# ads1292_Dorokhov.net
KiCad netlist of a schematic drawn in EAGLE
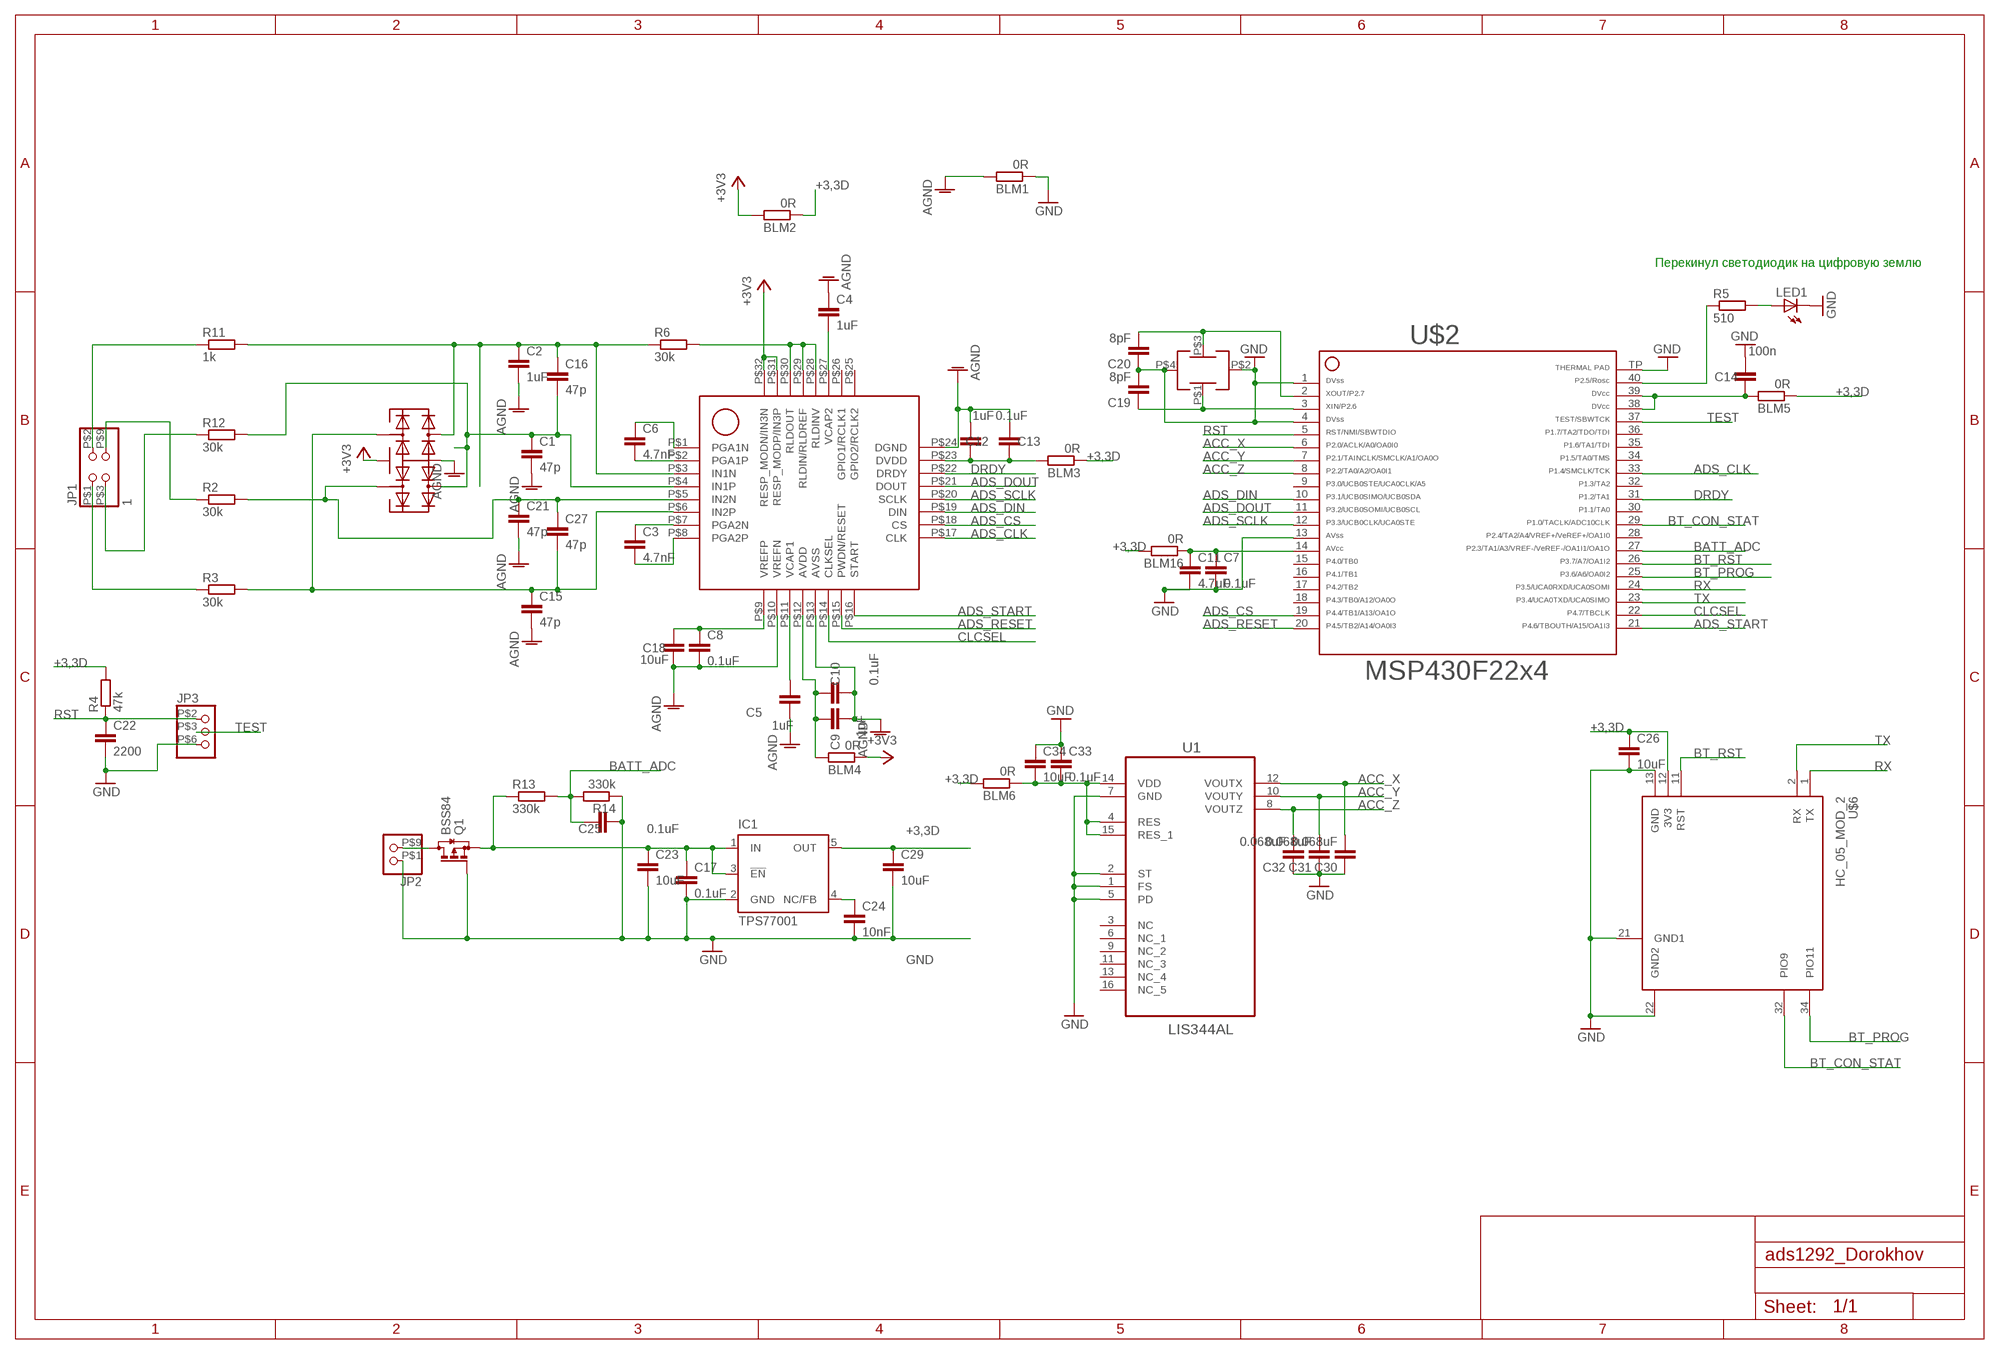
[diagram p0: schematic, sheet 1]

(export (version "E")
  (design (tool "Eeschema 10.0.6"))
  (components
    (comp (ref "BLM1")
      (value "0R")
      (footprint "eagle-import:SMD_0402")
      (libsource (lib "eagle-import") (part "RES0402"))
    )
    (comp (ref "BLM2")
      (value "0R")
      (footprint "eagle-import:SMD_0402")
      (libsource (lib "eagle-import") (part "RES0402"))
    )
    (comp (ref "BLM3")
      (value "0R")
      (footprint "eagle-import:SMD_0402")
      (libsource (lib "eagle-import") (part "RES0402"))
    )
    (comp (ref "BLM4")
      (value "0R")
      (footprint "eagle-import:SMD_0402")
      (libsource (lib "eagle-import") (part "RES0402"))
    )
    (comp (ref "BLM5")
      (value "0R")
      (footprint "eagle-import:SMD_0402")
      (libsource (lib "eagle-import") (part "RES0402"))
    )
    (comp (ref "BLM6")
      (value "0R")
      (footprint "eagle-import:SMD_0402")
      (libsource (lib "eagle-import") (part "RES0402"))
    )
    (comp (ref "BLM16")
      (value "0R")
      (footprint "eagle-import:SMD_0402")
      (libsource (lib "eagle-import") (part "RES0402"))
    )
    (comp (ref "C1")
      (value "47p")
      (footprint "eagle-import:SMD_0402")
      (libsource (lib "eagle-import") (part "CAP0402"))
    )
    (comp (ref "C2")
      (value "1uF")
      (footprint "eagle-import:SMD_0603")
      (libsource (lib "eagle-import") (part "CAP0603"))
    )
    (comp (ref "C3")
      (value "4.7nF")
      (footprint "eagle-import:SMD_0402")
      (libsource (lib "eagle-import") (part "CAP0402"))
    )
    (comp (ref "C4")
      (value "1uF")
      (footprint "eagle-import:SMD_0402")
      (libsource (lib "eagle-import") (part "CAP0402"))
    )
    (comp (ref "C5")
      (value "1uF")
      (footprint "eagle-import:SMD_0402")
      (libsource (lib "eagle-import") (part "CAP0402"))
    )
    (comp (ref "C6")
      (value "4.7nF")
      (footprint "eagle-import:SMD_0402")
      (libsource (lib "eagle-import") (part "CAP0402"))
    )
    (comp (ref "C7")
      (value "0.1uF")
      (footprint "eagle-import:SMD_0402")
      (libsource (lib "eagle-import") (part "CAP0402"))
    )
    (comp (ref "C8")
      (value "0.1uF")
      (footprint "eagle-import:SMD_0402")
      (libsource (lib "eagle-import") (part "CAP0402"))
    )
    (comp (ref "C9")
      (value "1uF")
      (footprint "eagle-import:SMD_0402")
      (libsource (lib "eagle-import") (part "CAP0402"))
    )
    (comp (ref "C10")
      (value "0.1uF")
      (footprint "eagle-import:SMD_0402")
      (libsource (lib "eagle-import") (part "CAP0402"))
    )
    (comp (ref "C11")
      (value "4.7uF")
      (footprint "eagle-import:SMD_0603")
      (libsource (lib "eagle-import") (part "CAP0603"))
    )
    (comp (ref "C12")
      (value "1uF")
      (footprint "eagle-import:SMD_0402")
      (libsource (lib "eagle-import") (part "CAP0402"))
    )
    (comp (ref "C13")
      (value "0.1uF")
      (footprint "eagle-import:SMD_0402")
      (libsource (lib "eagle-import") (part "CAP0402"))
    )
    (comp (ref "C14")
      (value "100n")
      (footprint "eagle-import:SMD_0402")
      (libsource (lib "eagle-import") (part "CAP0402"))
    )
    (comp (ref "C15")
      (value "47p")
      (footprint "eagle-import:SMD_0402")
      (libsource (lib "eagle-import") (part "CAP0402"))
    )
    (comp (ref "C16")
      (value "47p")
      (footprint "eagle-import:SMD_0402")
      (libsource (lib "eagle-import") (part "CAP0402"))
    )
    (comp (ref "C17")
      (value "0.1uF")
      (footprint "eagle-import:SMD_0402")
      (libsource (lib "eagle-import") (part "CAP0402"))
    )
    (comp (ref "C18")
      (value "10uF")
      (footprint "eagle-import:SMD_0603")
      (libsource (lib "eagle-import") (part "CAP0603"))
    )
    (comp (ref "C19")
      (value "8pF")
      (footprint "eagle-import:SMD_0402")
      (libsource (lib "eagle-import") (part "CAP0402"))
    )
    (comp (ref "C20")
      (value "8pF")
      (footprint "eagle-import:SMD_0402")
      (libsource (lib "eagle-import") (part "CAP0402"))
    )
    (comp (ref "C21")
      (value "47p")
      (footprint "eagle-import:SMD_0402")
      (libsource (lib "eagle-import") (part "CAP0402"))
    )
    (comp (ref "C22")
      (value "2200")
      (footprint "eagle-import:SMD_0402")
      (libsource (lib "eagle-import") (part "CAP0402"))
    )
    (comp (ref "C23")
      (value "10uF")
      (footprint "eagle-import:SMD_0603")
      (libsource (lib "eagle-import") (part "CAP0603"))
    )
    (comp (ref "C24")
      (value "10nF")
      (footprint "eagle-import:SMD_0402")
      (libsource (lib "eagle-import") (part "CAP0402"))
    )
    (comp (ref "C25")
      (value "0.1uF")
      (footprint "eagle-import:SMD_0402")
      (libsource (lib "eagle-import") (part "CAP0402"))
    )
    (comp (ref "C26")
      (value "10uF")
      (footprint "eagle-import:SMD_0603")
      (libsource (lib "eagle-import") (part "CAP0603"))
    )
    (comp (ref "C27")
      (value "47p")
      (footprint "eagle-import:SMD_0402")
      (libsource (lib "eagle-import") (part "CAP0402"))
    )
    (comp (ref "C29")
      (value "10uF")
      (footprint "eagle-import:SMD_0603")
      (libsource (lib "eagle-import") (part "CAP0603"))
    )
    (comp (ref "C30")
      (value "0.068uF")
      (footprint "eagle-import:SMD_0402")
      (libsource (lib "eagle-import") (part "CAP0402"))
    )
    (comp (ref "C31")
      (value "0.068uF")
      (footprint "eagle-import:SMD_0402")
      (libsource (lib "eagle-import") (part "CAP0402"))
    )
    (comp (ref "C32")
      (value "0.068uF")
      (footprint "eagle-import:SMD_0402")
      (libsource (lib "eagle-import") (part "CAP0402"))
    )
    (comp (ref "C33")
      (value "0.1uF")
      (footprint "eagle-import:SMD_0402")
      (libsource (lib "eagle-import") (part "CAP0402"))
    )
    (comp (ref "C34")
      (value "10uF")
      (footprint "eagle-import:SMD_0603")
      (libsource (lib "eagle-import") (part "CAP0603"))
    )
    (comp (ref "IC1")
      (value "TPS77001")
      (footprint "eagle-import:SOT23-DBV")
      (fields (field (name "MF") "TEXAS INSTRUMENTS") (field (name "MPN") "TPS77001DBVT"))
      (libsource (lib "eagle-import") (part "TPS77001"))
    )
    (comp (ref "JP1")
      (value "1")
      (footprint "eagle-import:PINHEAD_SMD_2X2_2,5")
      (libsource (lib "eagle-import") (part "PINHD-2X2SMD_2,5"))
    )
    (comp (ref "JP2")
      (value "PINHD-1X2SMD_2,5")
      (footprint "eagle-import:PINHEAD_SMD_2X1_2,5")
      (libsource (lib "eagle-import") (part "PINHD-1X2SMD_2,5"))
    )
    (comp (ref "JP3")
      (value "PINHD-1X3PROG_SMD")
      (footprint "eagle-import:PROG_CONNECTOR_3PIN")
      (libsource (lib "eagle-import") (part "PINHD-1X3PROG_SMD"))
    )
    (comp (ref "LED1")
      (value "LEDSML0603")
      (footprint "eagle-import:SML0603")
      (libsource (lib "eagle-import") (part "LEDSML0603"))
    )
    (comp (ref "Q1")
      (value "BSS84")
      (footprint "eagle-import:SOT23")
      (libsource (lib "eagle-import") (part "BSS84"))
    )
    (comp (ref "R2")
      (value "30k")
      (footprint "eagle-import:R0603")
      (libsource (lib "eagle-import") (part "RESR0603_WIDE"))
    )
    (comp (ref "R3")
      (value "30k")
      (footprint "eagle-import:R0603")
      (libsource (lib "eagle-import") (part "RESR0603_WIDE"))
    )
    (comp (ref "R4")
      (value "47k")
      (footprint "eagle-import:SMD_0402")
      (libsource (lib "eagle-import") (part "RES0402"))
    )
    (comp (ref "R5")
      (value "510")
      (footprint "eagle-import:SMD_0402")
      (libsource (lib "eagle-import") (part "RES0402"))
    )
    (comp (ref "R6")
      (value "30k")
      (footprint "eagle-import:SMD_0402")
      (libsource (lib "eagle-import") (part "RES0402"))
    )
    (comp (ref "R11")
      (value "1k")
      (footprint "eagle-import:R0603")
      (libsource (lib "eagle-import") (part "RESR0603_WIDE"))
    )
    (comp (ref "R12")
      (value "30k")
      (footprint "eagle-import:R0603")
      (libsource (lib "eagle-import") (part "RESR0603_WIDE"))
    )
    (comp (ref "R13")
      (value "330k")
      (footprint "eagle-import:SMD_0402")
      (libsource (lib "eagle-import") (part "RES0402"))
    )
    (comp (ref "R14")
      (value "330k")
      (footprint "eagle-import:SMD_0402")
      (libsource (lib "eagle-import") (part "RES0402"))
    )
    (comp (ref "U$1")
      (value "ADS1292TQFP-32")
      (footprint "eagle-import:TQFP-32")
      (libsource (lib "eagle-import") (part "ADS1292TQFP-32"))
    )
    (comp (ref "U$2")
      (value "F22X4---RHA40")
      (footprint "eagle-import:RHA40")
      (libsource (lib "eagle-import") (part "F22X4---RHA40"))
    )
    (comp (ref "U$3")
      (value "ECS_16_CRYSTAL")
      (footprint "eagle-import:ECS_16_CRYSTAL")
      (libsource (lib "eagle-import") (part "ECS_16_CRYSTAL"))
    )
    (comp (ref "U$4")
      (value "DALC208")
      (footprint "eagle-import:SOT23-6")
      (libsource (lib "eagle-import") (part "DALC208"))
    )
    (comp (ref "U$6")
      (value "HC_05_MOD_2")
      (footprint "eagle-import:BLUETOOTH_SMD_MOD2")
      (libsource (lib "eagle-import") (part "HC_05_MOD_2"))
    )
    (comp (ref "U1")
      (value "LIS344AL")
      (footprint "eagle-import:LGA16R65P4X4_400X400X160")
      (libsource (lib "eagle-import") (part "LIS344AL"))
    )
  )
  (nets
    (net (code "1") (name "+3V3") (class "Default")
      (node (ref "BLM2") (pin "P$4") (pinfunction "2_P$4") (pintype "passive"))
      (node (ref "BLM4") (pin "P$3") (pinfunction "1_P$3") (pintype "passive"))
      (node (ref "U$1") (pin "P$31") (pinfunction "RESP_MODP/IN3P_P$31") (pintype "bidirectional"))
      (node (ref "U$1") (pin "P$32") (pinfunction "RESP_MODN/IN3N_P$32") (pintype "bidirectional"))
      (node (ref "U$4") (pin "2") (pinfunction "2_2") (pintype "passive"))
    )
    (net (code "2") (name "/+3,3D") (class "Default")
      (node (ref "BLM16") (pin "P$4") (pinfunction "2_P$4") (pintype "passive"))
      (node (ref "BLM2") (pin "P$3") (pinfunction "1_P$3") (pintype "passive"))
      (node (ref "BLM3") (pin "P$3") (pinfunction "1_P$3") (pintype "passive"))
      (node (ref "BLM5") (pin "P$3") (pinfunction "1_P$3") (pintype "passive"))
      (node (ref "BLM6") (pin "P$4") (pinfunction "2_P$4") (pintype "passive"))
      (node (ref "C26") (pin "P$1") (pinfunction "1_P$1") (pintype "passive"))
      (node (ref "C29") (pin "P$1") (pinfunction "1_P$1") (pintype "passive"))
      (node (ref "IC1") (pin "5") (pinfunction "OUT_5") (pintype "passive"))
      (node (ref "R4") (pin "P$4") (pinfunction "2_P$4") (pintype "passive"))
      (node (ref "U$6") (pin "12") (pinfunction "3V3_12") (pintype "bidirectional"))
    )
    (net (code "3") (name "/ACC_X") (class "Default")
      (node (ref "C30") (pin "P$4") (pinfunction "2_P$4") (pintype "passive"))
      (node (ref "U$2") (pin "6") (pinfunction "6_6") (pintype "bidirectional"))
      (node (ref "U1") (pin "12") (pinfunction "VOUTX_12") (pintype "output"))
    )
    (net (code "4") (name "/ACC_Y") (class "Default")
      (node (ref "C31") (pin "P$4") (pinfunction "2_P$4") (pintype "passive"))
      (node (ref "U$2") (pin "7") (pinfunction "7_7") (pintype "bidirectional"))
      (node (ref "U1") (pin "10") (pinfunction "VOUTY_10") (pintype "output"))
    )
    (net (code "5") (name "/ACC_Z") (class "Default")
      (node (ref "C32") (pin "P$4") (pinfunction "2_P$4") (pintype "passive"))
      (node (ref "U$2") (pin "8") (pinfunction "8_8") (pintype "bidirectional"))
      (node (ref "U1") (pin "8") (pinfunction "VOUTZ_8") (pintype "output"))
    )
    (net (code "6") (name "/ADS_CLK") (class "Default")
      (node (ref "U$1") (pin "P$17") (pinfunction "CLK_P$17") (pintype "bidirectional"))
      (node (ref "U$2") (pin "33") (pinfunction "33_33") (pintype "bidirectional"))
    )
    (net (code "7") (name "/ADS_CS") (class "Default")
      (node (ref "U$1") (pin "P$18") (pinfunction "CS_P$18") (pintype "bidirectional"))
      (node (ref "U$2") (pin "19") (pinfunction "19_19") (pintype "bidirectional"))
    )
    (net (code "8") (name "/ADS_DIN") (class "Default")
      (node (ref "U$1") (pin "P$19") (pinfunction "DIN_P$19") (pintype "bidirectional"))
      (node (ref "U$2") (pin "10") (pinfunction "10_10") (pintype "bidirectional"))
    )
    (net (code "9") (name "/ADS_DOUT") (class "Default")
      (node (ref "U$1") (pin "P$21") (pinfunction "DOUT_P$21") (pintype "bidirectional"))
      (node (ref "U$2") (pin "11") (pinfunction "11_11") (pintype "bidirectional"))
    )
    (net (code "10") (name "/ADS_RESET") (class "Default")
      (node (ref "U$1") (pin "P$15") (pinfunction "PWDN/RESET_P$15") (pintype "bidirectional"))
      (node (ref "U$2") (pin "20") (pinfunction "20_20") (pintype "bidirectional"))
    )
    (net (code "11") (name "/ADS_SCLK") (class "Default")
      (node (ref "U$1") (pin "P$20") (pinfunction "SCLK_P$20") (pintype "bidirectional"))
      (node (ref "U$2") (pin "12") (pinfunction "12_12") (pintype "bidirectional"))
    )
    (net (code "12") (name "/ADS_START") (class "Default")
      (node (ref "U$1") (pin "P$16") (pinfunction "START_P$16") (pintype "bidirectional"))
      (node (ref "U$2") (pin "21") (pinfunction "21_21") (pintype "bidirectional"))
    )
    (net (code "13") (name "/BATT_ADC") (class "Default")
      (node (ref "C25") (pin "P$3") (pinfunction "1_P$3") (pintype "passive"))
      (node (ref "R13") (pin "P$4") (pinfunction "2_P$4") (pintype "passive"))
      (node (ref "R14") (pin "P$4") (pinfunction "2_P$4") (pintype "passive"))
      (node (ref "U$2") (pin "27") (pinfunction "27_27") (pintype "bidirectional"))
    )
    (net (code "14") (name "/BT_CON_STAT") (class "Default")
      (node (ref "U$2") (pin "29") (pinfunction "29_29") (pintype "bidirectional"))
      (node (ref "U$6") (pin "32") (pinfunction "PIO9_32") (pintype "bidirectional"))
    )
    (net (code "15") (name "/BT_PROG") (class "Default")
      (node (ref "U$2") (pin "25") (pinfunction "25_25") (pintype "bidirectional"))
      (node (ref "U$6") (pin "34") (pinfunction "PIO11_34") (pintype "bidirectional"))
    )
    (net (code "16") (name "/BT_RST") (class "Default")
      (node (ref "U$2") (pin "26") (pinfunction "26_26") (pintype "bidirectional"))
      (node (ref "U$6") (pin "11") (pinfunction "RST_11") (pintype "bidirectional"))
    )
    (net (code "17") (name "/CLCSEL") (class "Default")
      (node (ref "U$1") (pin "P$14") (pinfunction "CLKSEL_P$14") (pintype "bidirectional"))
      (node (ref "U$2") (pin "22") (pinfunction "22_22") (pintype "bidirectional"))
    )
    (net (code "18") (name "/DRDY") (class "Default")
      (node (ref "U$1") (pin "P$22") (pinfunction "DRDY_P$22") (pintype "bidirectional"))
      (node (ref "U$2") (pin "31") (pinfunction "31_31") (pintype "bidirectional"))
    )
    (net (code "19") (name "/RST") (class "Default")
      (node (ref "C22") (pin "P$3") (pinfunction "1_P$3") (pintype "passive"))
      (node (ref "JP3") (pin "P$2") (pinfunction "1_P$2") (pintype "passive"))
      (node (ref "R4") (pin "P$3") (pinfunction "1_P$3") (pintype "passive"))
      (node (ref "U$2") (pin "5") (pinfunction "5_5") (pintype "bidirectional"))
    )
    (net (code "20") (name "/RX") (class "Default")
      (node (ref "U$2") (pin "24") (pinfunction "24_24") (pintype "bidirectional"))
      (node (ref "U$6") (pin "1") (pinfunction "TX_1") (pintype "bidirectional"))
    )
    (net (code "21") (name "/TEST") (class "Default")
      (node (ref "JP3") (pin "P$3") (pinfunction "2_P$3") (pintype "passive"))
      (node (ref "U$2") (pin "37") (pinfunction "37_37") (pintype "input"))
    )
    (net (code "22") (name "/TX") (class "Default")
      (node (ref "U$2") (pin "23") (pinfunction "23_23") (pintype "bidirectional"))
      (node (ref "U$6") (pin "2") (pinfunction "RX_2") (pintype "bidirectional"))
    )
    (net (code "23") (name "AGND") (class "Default")
      (node (ref "BLM1") (pin "P$4") (pinfunction "2_P$4") (pintype "passive"))
      (node (ref "C1") (pin "P$4") (pinfunction "2_P$4") (pintype "passive"))
      (node (ref "C10") (pin "P$4") (pinfunction "2_P$4") (pintype "passive"))
      (node (ref "C12") (pin "P$4") (pinfunction "2_P$4") (pintype "passive"))
      (node (ref "C13") (pin "P$4") (pinfunction "2_P$4") (pintype "passive"))
      (node (ref "C15") (pin "P$4") (pinfunction "2_P$4") (pintype "passive"))
      (node (ref "C18") (pin "P$2") (pinfunction "2_P$2") (pintype "passive"))
      (node (ref "C2") (pin "P$2") (pinfunction "2_P$2") (pintype "passive"))
      (node (ref "C21") (pin "P$4") (pinfunction "2_P$4") (pintype "passive"))
      (node (ref "C4") (pin "P$3") (pinfunction "1_P$3") (pintype "passive"))
      (node (ref "C5") (pin "P$4") (pinfunction "2_P$4") (pintype "passive"))
      (node (ref "C8") (pin "P$4") (pinfunction "2_P$4") (pintype "passive"))
      (node (ref "C9") (pin "P$4") (pinfunction "2_P$4") (pintype "passive"))
      (node (ref "U$1") (pin "P$10") (pinfunction "VREFN_P$10") (pintype "bidirectional"))
      (node (ref "U$1") (pin "P$13") (pinfunction "AVSS_P$13") (pintype "bidirectional"))
      (node (ref "U$1") (pin "P$24") (pinfunction "DGND_P$24") (pintype "bidirectional"))
      (node (ref "U$4") (pin "5") (pinfunction "5_5") (pintype "passive"))
    )
    (net (code "24") (name "GND") (class "Default")
      (node (ref "BLM1") (pin "P$3") (pinfunction "1_P$3") (pintype "passive"))
      (node (ref "C11") (pin "P$2") (pinfunction "2_P$2") (pintype "passive"))
      (node (ref "C14") (pin "P$4") (pinfunction "2_P$4") (pintype "passive"))
      (node (ref "C17") (pin "P$4") (pinfunction "2_P$4") (pintype "passive"))
      (node (ref "C19") (pin "P$4") (pinfunction "2_P$4") (pintype "passive"))
      (node (ref "C20") (pin "P$3") (pinfunction "1_P$3") (pintype "passive"))
      (node (ref "C22") (pin "P$4") (pinfunction "2_P$4") (pintype "passive"))
      (node (ref "C23") (pin "P$2") (pinfunction "2_P$2") (pintype "passive"))
      (node (ref "C24") (pin "P$4") (pinfunction "2_P$4") (pintype "passive"))
      (node (ref "C25") (pin "P$4") (pinfunction "2_P$4") (pintype "passive"))
      (node (ref "C26") (pin "P$2") (pinfunction "2_P$2") (pintype "passive"))
      (node (ref "C29") (pin "P$2") (pinfunction "2_P$2") (pintype "passive"))
      (node (ref "C30") (pin "P$3") (pinfunction "1_P$3") (pintype "passive"))
      (node (ref "C31") (pin "P$3") (pinfunction "1_P$3") (pintype "passive"))
      (node (ref "C32") (pin "P$3") (pinfunction "1_P$3") (pintype "passive"))
      (node (ref "C33") (pin "P$3") (pinfunction "1_P$3") (pintype "passive"))
      (node (ref "C34") (pin "P$1") (pinfunction "1_P$1") (pintype "passive"))
      (node (ref "C7") (pin "P$4") (pinfunction "2_P$4") (pintype "passive"))
      (node (ref "IC1") (pin "2") (pinfunction "GND_2") (pintype "power_in"))
      (node (ref "JP2") (pin "P$1") (pinfunction "1_P$1") (pintype "passive"))
      (node (ref "JP3") (pin "P$6") (pinfunction "3_P$6") (pintype "passive"))
      (node (ref "LED1") (pin "C") (pinfunction "C_C") (pintype "passive"))
      (node (ref "Q1") (pin "1") (pinfunction "G_1") (pintype "passive"))
      (node (ref "R14") (pin "P$3") (pinfunction "1_P$3") (pintype "passive"))
      (node (ref "U$2") (pin "1") (pinfunction "1_1") (pintype "power_in"))
      (node (ref "U$2") (pin "13") (pinfunction "13_13") (pintype "power_in"))
      (node (ref "U$2") (pin "4") (pinfunction "4_4") (pintype "power_in"))
      (node (ref "U$2") (pin "TP") (pinfunction "TP_TP") (pintype "power_in"))
      (node (ref "U$3") (pin "P$2") (pinfunction "P$2_P$2") (pintype "bidirectional"))
      (node (ref "U$3") (pin "P$4") (pinfunction "P$3_P$4") (pintype "bidirectional"))
      (node (ref "U$6") (pin "13") (pinfunction "GND_13") (pintype "bidirectional"))
      (node (ref "U$6") (pin "21") (pinfunction "GND1_21") (pintype "bidirectional"))
      (node (ref "U$6") (pin "22") (pinfunction "GND2_22") (pintype "bidirectional"))
      (node (ref "U1") (pin "1") (pinfunction "FS_1") (pintype "passive"))
      (node (ref "U1") (pin "2") (pinfunction "ST_2") (pintype "passive"))
      (node (ref "U1") (pin "5") (pinfunction "PD_5") (pintype "passive"))
      (node (ref "U1") (pin "7") (pinfunction "GND_7") (pintype "passive"))
    )
    (net (code "25") (name "Net-(BLM3-2)") (class "Default")
      (node (ref "BLM3") (pin "P$4") (pinfunction "2_P$4") (pintype "passive"))
      (node (ref "C12") (pin "P$3") (pinfunction "1_P$3") (pintype "passive"))
      (node (ref "C13") (pin "P$3") (pinfunction "1_P$3") (pintype "passive"))
      (node (ref "U$1") (pin "P$23") (pinfunction "DVDD_P$23") (pintype "bidirectional"))
    )
    (net (code "26") (name "Net-(BLM4-2)") (class "Default")
      (node (ref "BLM4") (pin "P$4") (pinfunction "2_P$4") (pintype "passive"))
      (node (ref "C10") (pin "P$3") (pinfunction "1_P$3") (pintype "passive"))
      (node (ref "C9") (pin "P$3") (pinfunction "1_P$3") (pintype "passive"))
      (node (ref "U$1") (pin "P$12") (pinfunction "AVDD_P$12") (pintype "bidirectional"))
    )
    (net (code "27") (name "Net-(BLM5-2)") (class "Default")
      (node (ref "BLM5") (pin "P$4") (pinfunction "2_P$4") (pintype "passive"))
      (node (ref "C14") (pin "P$3") (pinfunction "1_P$3") (pintype "passive"))
      (node (ref "U$2") (pin "38") (pinfunction "38_38") (pintype "power_in"))
      (node (ref "U$2") (pin "39") (pinfunction "39_39") (pintype "power_in"))
    )
    (net (code "28") (name "Net-(BLM6-1)") (class "Default")
      (node (ref "BLM6") (pin "P$3") (pinfunction "1_P$3") (pintype "passive"))
      (node (ref "C33") (pin "P$4") (pinfunction "2_P$4") (pintype "passive"))
      (node (ref "C34") (pin "P$2") (pinfunction "2_P$2") (pintype "passive"))
      (node (ref "U1") (pin "14") (pinfunction "VDD_14") (pintype "power_in"))
      (node (ref "U1") (pin "15") (pinfunction "RES_1_15") (pintype "passive"))
      (node (ref "U1") (pin "4") (pinfunction "RES_4") (pintype "passive"))
    )
    (net (code "29") (name "Net-(BLM16-1)") (class "Default")
      (node (ref "BLM16") (pin "P$3") (pinfunction "1_P$3") (pintype "passive"))
      (node (ref "C11") (pin "P$1") (pinfunction "1_P$1") (pintype "passive"))
      (node (ref "C7") (pin "P$3") (pinfunction "1_P$3") (pintype "passive"))
      (node (ref "U$2") (pin "14") (pinfunction "14_14") (pintype "power_in"))
    )
    (net (code "30") (name "Net-(C1-1)") (class "Default")
      (node (ref "C1") (pin "P$3") (pinfunction "1_P$3") (pintype "passive"))
      (node (ref "C16") (pin "P$4") (pinfunction "2_P$4") (pintype "passive"))
      (node (ref "R12") (pin "2") (pinfunction "2_2") (pintype "passive"))
      (node (ref "U$1") (pin "P$4") (pinfunction "IN1P_P$4") (pintype "bidirectional"))
      (node (ref "U$4") (pin "6") (pinfunction "6_6") (pintype "passive"))
    )
    (net (code "31") (name "Net-(C3-1)") (class "Default")
      (node (ref "C3") (pin "P$3") (pinfunction "1_P$3") (pintype "passive"))
      (node (ref "U$1") (pin "P$7") (pinfunction "PGA2N_P$7") (pintype "bidirectional"))
    )
    (net (code "32") (name "Net-(C3-2)") (class "Default")
      (node (ref "C3") (pin "P$4") (pinfunction "2_P$4") (pintype "passive"))
      (node (ref "U$1") (pin "P$8") (pinfunction "PGA2P_P$8") (pintype "bidirectional"))
    )
    (net (code "33") (name "Net-(C4-2)") (class "Default")
      (node (ref "C4") (pin "P$4") (pinfunction "2_P$4") (pintype "passive"))
      (node (ref "U$1") (pin "P$27") (pinfunction "VCAP2_P$27") (pintype "bidirectional"))
    )
    (net (code "34") (name "Net-(C5-1)") (class "Default")
      (node (ref "C5") (pin "P$3") (pinfunction "1_P$3") (pintype "passive"))
      (node (ref "U$1") (pin "P$11") (pinfunction "VCAP1_P$11") (pintype "bidirectional"))
    )
    (net (code "35") (name "Net-(C6-1)") (class "Default")
      (node (ref "C6") (pin "P$3") (pinfunction "1_P$3") (pintype "passive"))
      (node (ref "U$1") (pin "P$1") (pinfunction "PGA1N_P$1") (pintype "bidirectional"))
    )
    (net (code "36") (name "Net-(C6-2)") (class "Default")
      (node (ref "C6") (pin "P$4") (pinfunction "2_P$4") (pintype "passive"))
      (node (ref "U$1") (pin "P$2") (pinfunction "PGA1P_P$2") (pintype "bidirectional"))
    )
    (net (code "37") (name "Net-(C15-1)") (class "Default")
      (node (ref "C15") (pin "P$3") (pinfunction "1_P$3") (pintype "passive"))
      (node (ref "C27") (pin "P$4") (pinfunction "2_P$4") (pintype "passive"))
      (node (ref "R3") (pin "2") (pinfunction "2_2") (pintype "passive"))
      (node (ref "U$1") (pin "P$6") (pinfunction "IN2P_P$6") (pintype "bidirectional"))
      (node (ref "U$4") (pin "1") (pinfunction "1_1") (pintype "passive"))
    )
    (net (code "38") (name "Net-(C16-1)") (class "Default")
      (node (ref "C16") (pin "P$3") (pinfunction "1_P$3") (pintype "passive"))
      (node (ref "C2") (pin "P$1") (pinfunction "1_P$1") (pintype "passive"))
      (node (ref "R11") (pin "2") (pinfunction "2_2") (pintype "passive"))
      (node (ref "R6") (pin "P$3") (pinfunction "1_P$3") (pintype "passive"))
      (node (ref "U$1") (pin "P$3") (pinfunction "IN1N_P$3") (pintype "bidirectional"))
      (node (ref "U$4") (pin "4") (pinfunction "4_4") (pintype "passive"))
    )
    (net (code "39") (name "Net-(C17-1)") (class "Default")
      (node (ref "C17") (pin "P$3") (pinfunction "1_P$3") (pintype "passive"))
      (node (ref "C23") (pin "P$1") (pinfunction "1_P$1") (pintype "passive"))
      (node (ref "IC1") (pin "1") (pinfunction "IN_1") (pintype "input"))
      (node (ref "IC1") (pin "3") (pinfunction "~{EN}_3") (pintype "input"))
      (node (ref "Q1") (pin "2") (pinfunction "S_2") (pintype "passive"))
      (node (ref "R13") (pin "P$3") (pinfunction "1_P$3") (pintype "passive"))
    )
    (net (code "40") (name "Net-(C18-1)") (class "Default")
      (node (ref "C18") (pin "P$1") (pinfunction "1_P$1") (pintype "passive"))
      (node (ref "C8") (pin "P$3") (pinfunction "1_P$3") (pintype "passive"))
      (node (ref "U$1") (pin "P$9") (pinfunction "VREFP_P$9") (pintype "bidirectional"))
    )
    (net (code "41") (name "Net-(C19-1)") (class "Default")
      (node (ref "C19") (pin "P$3") (pinfunction "1_P$3") (pintype "passive"))
      (node (ref "U$2") (pin "3") (pinfunction "3_3") (pintype "bidirectional"))
      (node (ref "U$3") (pin "P$1") (pinfunction "P$1_P$1") (pintype "bidirectional"))
    )
    (net (code "42") (name "Net-(C20-2)") (class "Default")
      (node (ref "C20") (pin "P$4") (pinfunction "2_P$4") (pintype "passive"))
      (node (ref "U$2") (pin "2") (pinfunction "2_2") (pintype "bidirectional"))
      (node (ref "U$3") (pin "P$3") (pinfunction "P$4_P$3") (pintype "bidirectional"))
    )
    (net (code "43") (name "Net-(C21-1)") (class "Default")
      (node (ref "C21") (pin "P$3") (pinfunction "1_P$3") (pintype "passive"))
      (node (ref "C27") (pin "P$3") (pinfunction "1_P$3") (pintype "passive"))
      (node (ref "R2") (pin "2") (pinfunction "2_2") (pintype "passive"))
      (node (ref "U$1") (pin "P$5") (pinfunction "IN2N_P$5") (pintype "bidirectional"))
      (node (ref "U$4") (pin "3") (pinfunction "3_3") (pintype "passive"))
    )
    (net (code "44") (name "Net-(C24-1)") (class "Default")
      (node (ref "C24") (pin "P$3") (pinfunction "1_P$3") (pintype "passive"))
      (node (ref "IC1") (pin "4") (pinfunction "NC/FB_4") (pintype "passive"))
    )
    (net (code "45") (name "Net-(JP1-1)") (class "Default")
      (node (ref "JP1") (pin "P$1") (pinfunction "1_P$1") (pintype "passive"))
      (node (ref "R3") (pin "1") (pinfunction "1_1") (pintype "passive"))
    )
    (net (code "46") (name "Net-(JP1-2)") (class "Default")
      (node (ref "JP1") (pin "P$2") (pinfunction "2_P$2") (pintype "passive"))
      (node (ref "R11") (pin "1") (pinfunction "1_1") (pintype "passive"))
    )
    (net (code "47") (name "Net-(JP1-3)") (class "Default")
      (node (ref "JP1") (pin "P$3") (pinfunction "3_P$3") (pintype "passive"))
      (node (ref "R12") (pin "1") (pinfunction "1_1") (pintype "passive"))
    )
    (net (code "48") (name "Net-(JP1-4)") (class "Default")
      (node (ref "JP1") (pin "P$9") (pinfunction "4_P$9") (pintype "passive"))
      (node (ref "R2") (pin "1") (pinfunction "1_1") (pintype "passive"))
    )
    (net (code "49") (name "Net-(JP2-2)") (class "Default")
      (node (ref "JP2") (pin "P$9") (pinfunction "2_P$9") (pintype "passive"))
      (node (ref "Q1") (pin "3") (pinfunction "D_3") (pintype "passive"))
    )
    (net (code "50") (name "Net-(R5-1)") (class "Default")
      (node (ref "R5") (pin "P$3") (pinfunction "1_P$3") (pintype "passive"))
      (node (ref "U$2") (pin "40") (pinfunction "40_40") (pintype "bidirectional"))
    )
    (net (code "51") (name "Net-(R5-2)") (class "Default")
      (node (ref "LED1") (pin "A") (pinfunction "A_A") (pintype "passive"))
      (node (ref "R5") (pin "P$4") (pinfunction "2_P$4") (pintype "passive"))
    )
    (net (code "52") (name "Net-(R6-2)") (class "Default")
      (node (ref "R6") (pin "P$4") (pinfunction "2_P$4") (pintype "passive"))
      (node (ref "U$1") (pin "P$28") (pinfunction "RLDINV_P$28") (pintype "bidirectional"))
      (node (ref "U$1") (pin "P$29") (pinfunction "RLDIN/RLDREF_P$29") (pintype "bidirectional"))
      (node (ref "U$1") (pin "P$30") (pinfunction "RLDOUT_P$30") (pintype "bidirectional"))
    )
    (net (code "53") (name "unconnected-(U$1-GPIO1{slash}RCLK1-PadP$26)") (class "Default")
      (node (ref "U$1") (pin "P$26") (pinfunction "GPIO1/RCLK1_P$26") (pintype "bidirectional"))
    )
    (net (code "54") (name "unconnected-(U$1-GPIO2{slash}RCLK2-PadP$25)") (class "Default")
      (node (ref "U$1") (pin "P$25") (pinfunction "GPIO2/RCLK2_P$25") (pintype "bidirectional"))
    )
    (net (code "55") (name "unconnected-(U$2-Pad9)") (class "Default")
      (node (ref "U$2") (pin "9") (pinfunction "9_9") (pintype "bidirectional"))
    )
    (net (code "56") (name "unconnected-(U$2-Pad15)") (class "Default")
      (node (ref "U$2") (pin "15") (pinfunction "15_15") (pintype "bidirectional"))
    )
    (net (code "57") (name "unconnected-(U$2-Pad16)") (class "Default")
      (node (ref "U$2") (pin "16") (pinfunction "16_16") (pintype "bidirectional"))
    )
    (net (code "58") (name "unconnected-(U$2-Pad17)") (class "Default")
      (node (ref "U$2") (pin "17") (pinfunction "17_17") (pintype "bidirectional"))
    )
    (net (code "59") (name "unconnected-(U$2-Pad18)") (class "Default")
      (node (ref "U$2") (pin "18") (pinfunction "18_18") (pintype "bidirectional"))
    )
    (net (code "60") (name "unconnected-(U$2-Pad28)") (class "Default")
      (node (ref "U$2") (pin "28") (pinfunction "28_28") (pintype "bidirectional"))
    )
    (net (code "61") (name "unconnected-(U$2-Pad30)") (class "Default")
      (node (ref "U$2") (pin "30") (pinfunction "30_30") (pintype "bidirectional"))
    )
    (net (code "62") (name "unconnected-(U$2-Pad32)") (class "Default")
      (node (ref "U$2") (pin "32") (pinfunction "32_32") (pintype "bidirectional"))
    )
    (net (code "63") (name "unconnected-(U$2-Pad34)") (class "Default")
      (node (ref "U$2") (pin "34") (pinfunction "34_34") (pintype "bidirectional"))
    )
    (net (code "64") (name "unconnected-(U$2-Pad35)") (class "Default")
      (node (ref "U$2") (pin "35") (pinfunction "35_35") (pintype "bidirectional"))
    )
    (net (code "65") (name "unconnected-(U$2-Pad36)") (class "Default")
      (node (ref "U$2") (pin "36") (pinfunction "36_36") (pintype "bidirectional"))
    )
    (net (code "66") (name "unconnected-(U1-NC-Pad3)") (class "Default")
      (node (ref "U1") (pin "3") (pinfunction "NC_3") (pintype "no_connect"))
    )
    (net (code "67") (name "unconnected-(U1-NC_1-Pad6)") (class "Default")
      (node (ref "U1") (pin "6") (pinfunction "NC_1_6") (pintype "no_connect"))
    )
    (net (code "68") (name "unconnected-(U1-NC_2-Pad9)") (class "Default")
      (node (ref "U1") (pin "9") (pinfunction "NC_2_9") (pintype "no_connect"))
    )
    (net (code "69") (name "unconnected-(U1-NC_3-Pad11)") (class "Default")
      (node (ref "U1") (pin "11") (pinfunction "NC_3_11") (pintype "no_connect"))
    )
    (net (code "70") (name "unconnected-(U1-NC_4-Pad13)") (class "Default")
      (node (ref "U1") (pin "13") (pinfunction "NC_4_13") (pintype "no_connect"))
    )
    (net (code "71") (name "unconnected-(U1-NC_5-Pad16)") (class "Default")
      (node (ref "U1") (pin "16") (pinfunction "NC_5_16") (pintype "no_connect"))
    )
  )
)
